# RPi.net
KiCad netlist of a schematic drawn in EAGLE
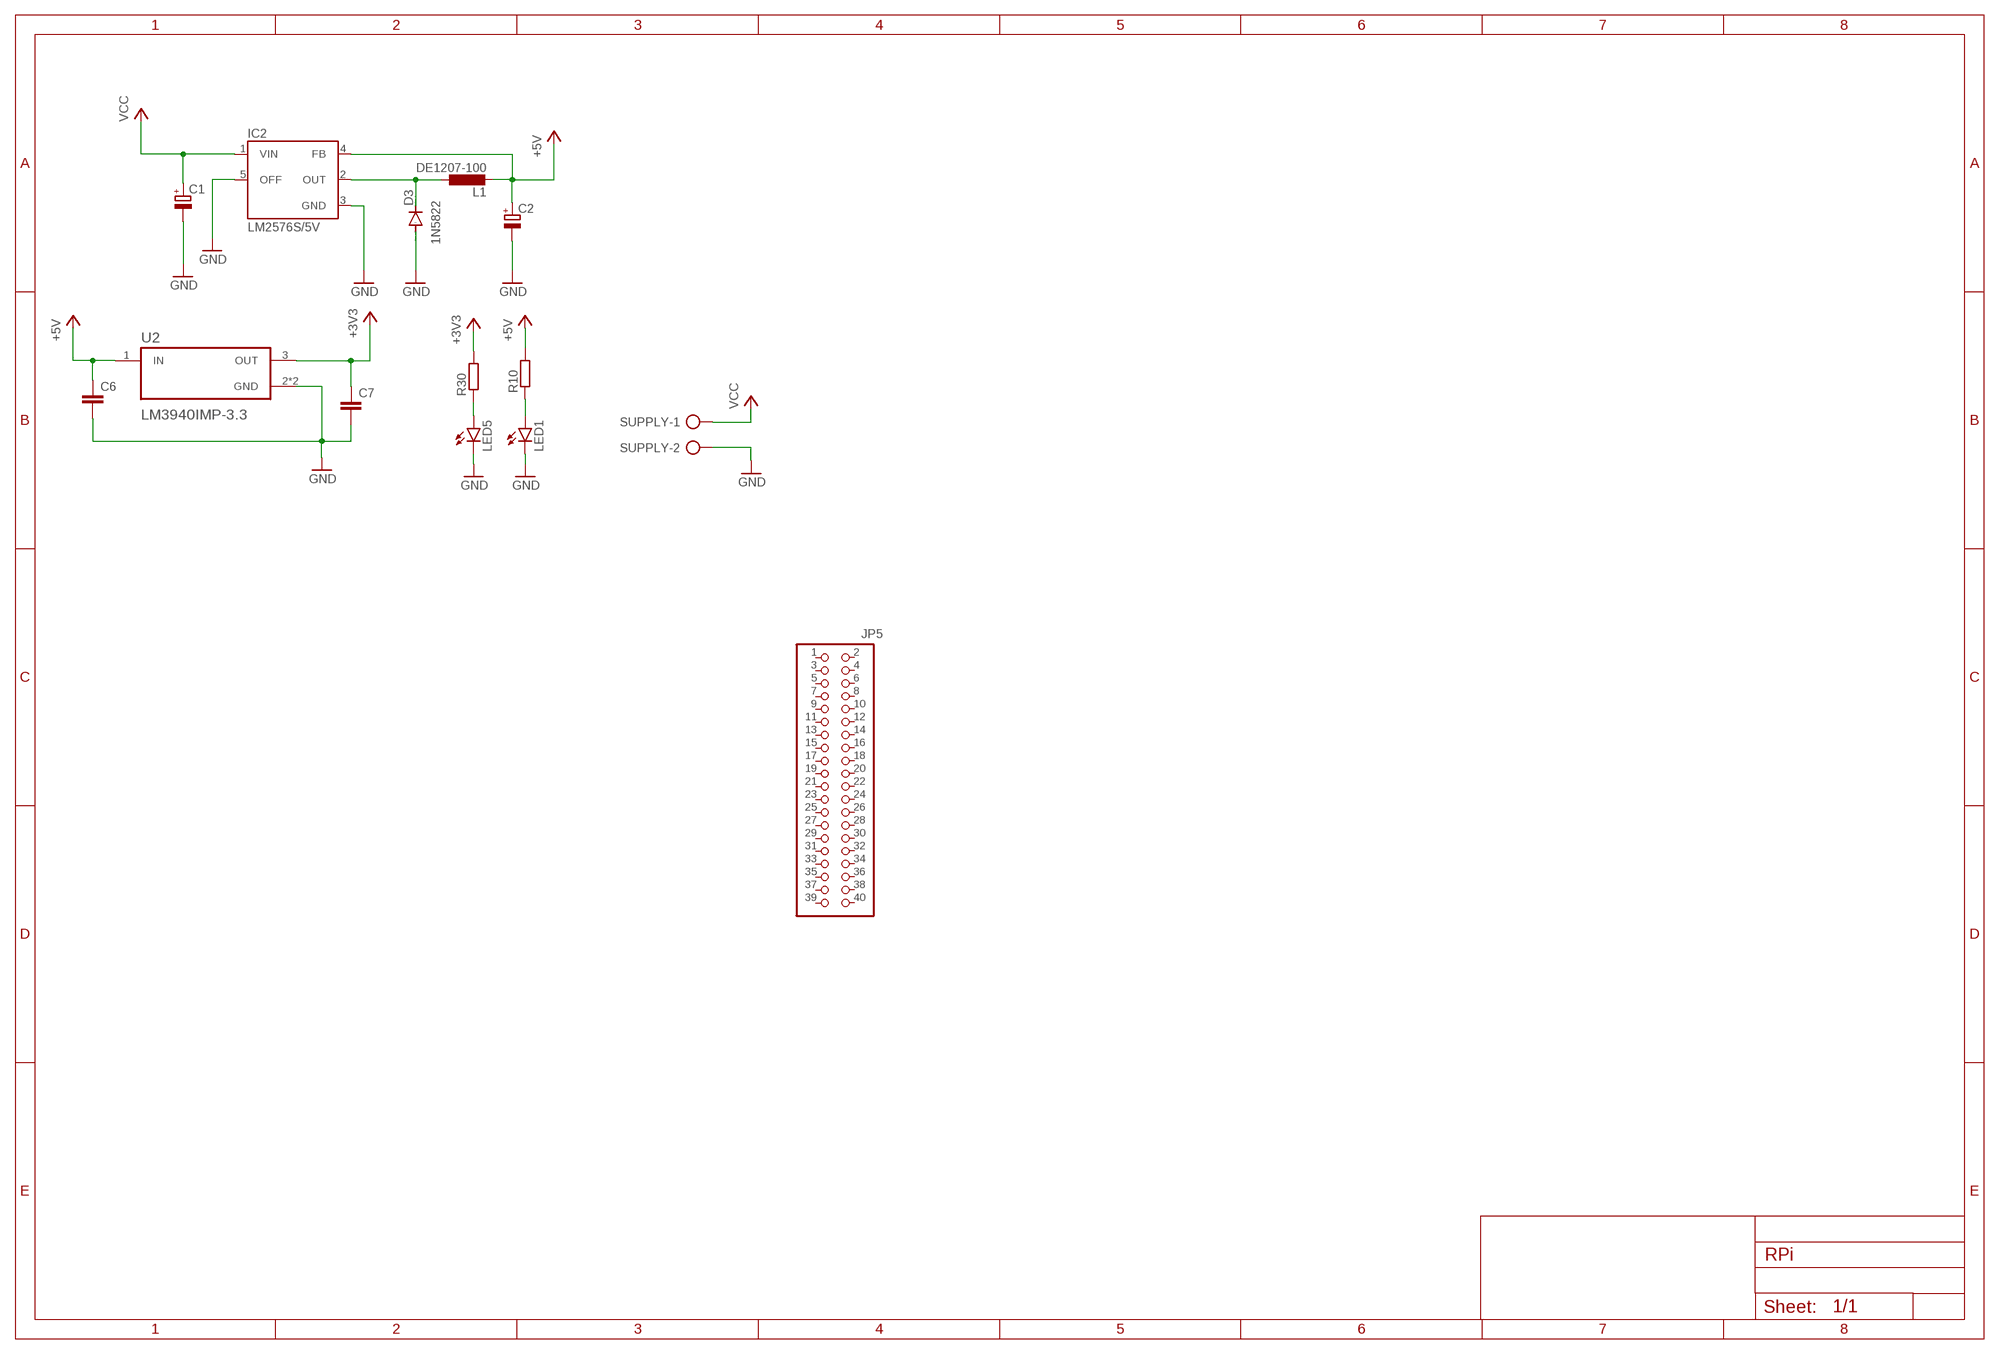
[diagram p0: schematic, sheet 1]

(export (version "E")
  (design (tool "Eeschema 10.0.6"))
  (components
    (comp (ref "C1")
      (value "CPOL-EUE2.5-6")
      (footprint "eagle-import:E2,5-6")
      (libsource (lib "eagle-import") (part "CPOL-EUE2.5-6"))
    )
    (comp (ref "C2")
      (value "CPOL-EUE2.5-6")
      (footprint "eagle-import:E2,5-6")
      (libsource (lib "eagle-import") (part "CPOL-EUE2.5-6"))
    )
    (comp (ref "C6")
      (value "C-EUC0805K")
      (footprint "eagle-import:C0805K")
      (libsource (lib "eagle-import") (part "C-EUC0805K"))
    )
    (comp (ref "C7")
      (value "C-EUC0805K")
      (footprint "eagle-import:C0805K")
      (libsource (lib "eagle-import") (part "C-EUC0805K"))
    )
    (comp (ref "D3")
      (value "1N5822")
      (footprint "eagle-import:DO41-10")
      (libsource (lib "eagle-import") (part "1N4004"))
    )
    (comp (ref "IC2")
      (value "LM2576S/5V")
      (footprint "eagle-import:TO263-5")
      (libsource (lib "eagle-import") (part "LM2576S"))
    )
    (comp (ref "JP5")
      (value "PINHD-2X20")
      (footprint "eagle-import:2X20")
      (libsource (lib "eagle-import") (part "PINHD-2X20"))
    )
    (comp (ref "L1")
      (value "DE1207-100")
      (footprint "eagle-import:DE1207")
      (libsource (lib "eagle-import") (part "DE1207-100"))
    )
    (comp (ref "LED1")
      (value "LEDSML0805")
      (footprint "eagle-import:SML0805")
      (libsource (lib "eagle-import") (part "LEDSML0805"))
    )
    (comp (ref "LED5")
      (value "LEDSML0805")
      (footprint "eagle-import:SML0805")
      (libsource (lib "eagle-import") (part "LEDSML0805"))
    )
    (comp (ref "R10")
      (value "R-EU_R0805")
      (footprint "eagle-import:R0805")
      (libsource (lib "eagle-import") (part "R-EU_R0805"))
    )
    (comp (ref "R30")
      (value "R-EU_R0805")
      (footprint "eagle-import:R0805")
      (libsource (lib "eagle-import") (part "R-EU_R0805"))
    )
    (comp (ref "SUPPLY")
      (value "AK500/2-H")
      (footprint "eagle-import:AK500_2-H")
      (libsource (lib "eagle-import") (part "AK500/2-H"))
    )
    (comp (ref "U2")
      (value "LM3940IMP-3.3")
      (footprint "eagle-import:SOT230P700X180-4N")
      (fields (field (name "MF") "Texas Instruments"))
      (libsource (lib "eagle-import") (part "LM3940IMP-3.3"))
    )
  )
  (nets
    (net (code "1") (name "+3V3") (class "Default")
      (node (ref "C7") (pin "1") (pinfunction "1_1") (pintype "passive"))
      (node (ref "R30") (pin "2") (pinfunction "2_2") (pintype "passive"))
      (node (ref "U2") (pin "3") (pinfunction "OUT_3") (pintype "output"))
    )
    (net (code "2") (name "+5V") (class "Default")
      (node (ref "C2") (pin "+") (pinfunction "+_+") (pintype "passive"))
      (node (ref "C6") (pin "1") (pinfunction "1_1") (pintype "passive"))
      (node (ref "IC2") (pin "4") (pinfunction "FB_4") (pintype "input"))
      (node (ref "L1") (pin "2") (pinfunction "2_2") (pintype "passive"))
      (node (ref "R10") (pin "2") (pinfunction "2_2") (pintype "passive"))
      (node (ref "U2") (pin "1") (pinfunction "IN_1") (pintype "input"))
    )
    (net (code "3") (name "GND") (class "Default")
      (node (ref "C1") (pin "-") (pinfunction "-_-") (pintype "passive"))
      (node (ref "C2") (pin "-") (pinfunction "-_-") (pintype "passive"))
      (node (ref "C6") (pin "2") (pinfunction "2_2") (pintype "passive"))
      (node (ref "C7") (pin "2") (pinfunction "2_2") (pintype "passive"))
      (node (ref "D3") (pin "A") (pinfunction "A_A") (pintype "passive"))
      (node (ref "IC2") (pin "3") (pinfunction "GND_3") (pintype "power_in"))
      (node (ref "IC2") (pin "5") (pinfunction "OFF_5") (pintype "input"))
      (node (ref "LED1") (pin "C") (pinfunction "C_C") (pintype "passive"))
      (node (ref "LED5") (pin "C") (pinfunction "C_C") (pintype "passive"))
      (node (ref "SUPPLY") (pin "2") (pinfunction "KL_2") (pintype "passive"))
      (node (ref "U2") (pin "2") (pinfunction "GND_2") (pintype "power_in"))
      (node (ref "U2") (pin "4") (pinfunction "GND_4") (pintype "power_in"))
    )
    (net (code "4") (name "Net-(IC2-OUT)") (class "Default")
      (node (ref "D3") (pin "C") (pinfunction "C_C") (pintype "passive"))
      (node (ref "IC2") (pin "2") (pinfunction "OUT_2") (pintype "output"))
      (node (ref "L1") (pin "1") (pinfunction "1_1") (pintype "passive"))
    )
    (net (code "5") (name "Net-(LED1-PadA)") (class "Default")
      (node (ref "LED1") (pin "A") (pinfunction "A_A") (pintype "passive"))
      (node (ref "R10") (pin "1") (pinfunction "1_1") (pintype "passive"))
    )
    (net (code "6") (name "Net-(LED5-PadA)") (class "Default")
      (node (ref "LED5") (pin "A") (pinfunction "A_A") (pintype "passive"))
      (node (ref "R30") (pin "1") (pinfunction "1_1") (pintype "passive"))
    )
    (net (code "7") (name "VCC") (class "Default")
      (node (ref "C1") (pin "+") (pinfunction "+_+") (pintype "passive"))
      (node (ref "IC2") (pin "1") (pinfunction "VIN_1") (pintype "power_in"))
      (node (ref "SUPPLY") (pin "1") (pinfunction "KL_1") (pintype "passive"))
    )
    (net (code "8") (name "unconnected-(JP5-Pad1)") (class "Default")
      (node (ref "JP5") (pin "1") (pinfunction "1_1") (pintype "passive"))
    )
    (net (code "9") (name "unconnected-(JP5-Pad2)") (class "Default")
      (node (ref "JP5") (pin "2") (pinfunction "2_2") (pintype "passive"))
    )
    (net (code "10") (name "unconnected-(JP5-Pad3)") (class "Default")
      (node (ref "JP5") (pin "3") (pinfunction "3_3") (pintype "passive"))
    )
    (net (code "11") (name "unconnected-(JP5-Pad4)") (class "Default")
      (node (ref "JP5") (pin "4") (pinfunction "4_4") (pintype "passive"))
    )
    (net (code "12") (name "unconnected-(JP5-Pad5)") (class "Default")
      (node (ref "JP5") (pin "5") (pinfunction "5_5") (pintype "passive"))
    )
    (net (code "13") (name "unconnected-(JP5-Pad6)") (class "Default")
      (node (ref "JP5") (pin "6") (pinfunction "6_6") (pintype "passive"))
    )
    (net (code "14") (name "unconnected-(JP5-Pad7)") (class "Default")
      (node (ref "JP5") (pin "7") (pinfunction "7_7") (pintype "passive"))
    )
    (net (code "15") (name "unconnected-(JP5-Pad8)") (class "Default")
      (node (ref "JP5") (pin "8") (pinfunction "8_8") (pintype "passive"))
    )
    (net (code "16") (name "unconnected-(JP5-Pad9)") (class "Default")
      (node (ref "JP5") (pin "9") (pinfunction "9_9") (pintype "passive"))
    )
    (net (code "17") (name "unconnected-(JP5-Pad10)") (class "Default")
      (node (ref "JP5") (pin "10") (pinfunction "10_10") (pintype "passive"))
    )
    (net (code "18") (name "unconnected-(JP5-Pad11)") (class "Default")
      (node (ref "JP5") (pin "11") (pinfunction "11_11") (pintype "passive"))
    )
    (net (code "19") (name "unconnected-(JP5-Pad12)") (class "Default")
      (node (ref "JP5") (pin "12") (pinfunction "12_12") (pintype "passive"))
    )
    (net (code "20") (name "unconnected-(JP5-Pad13)") (class "Default")
      (node (ref "JP5") (pin "13") (pinfunction "13_13") (pintype "passive"))
    )
    (net (code "21") (name "unconnected-(JP5-Pad14)") (class "Default")
      (node (ref "JP5") (pin "14") (pinfunction "14_14") (pintype "passive"))
    )
    (net (code "22") (name "unconnected-(JP5-Pad15)") (class "Default")
      (node (ref "JP5") (pin "15") (pinfunction "15_15") (pintype "passive"))
    )
    (net (code "23") (name "unconnected-(JP5-Pad16)") (class "Default")
      (node (ref "JP5") (pin "16") (pinfunction "16_16") (pintype "passive"))
    )
    (net (code "24") (name "unconnected-(JP5-Pad17)") (class "Default")
      (node (ref "JP5") (pin "17") (pinfunction "17_17") (pintype "passive"))
    )
    (net (code "25") (name "unconnected-(JP5-Pad18)") (class "Default")
      (node (ref "JP5") (pin "18") (pinfunction "18_18") (pintype "passive"))
    )
    (net (code "26") (name "unconnected-(JP5-Pad19)") (class "Default")
      (node (ref "JP5") (pin "19") (pinfunction "19_19") (pintype "passive"))
    )
    (net (code "27") (name "unconnected-(JP5-Pad20)") (class "Default")
      (node (ref "JP5") (pin "20") (pinfunction "20_20") (pintype "passive"))
    )
    (net (code "28") (name "unconnected-(JP5-Pad21)") (class "Default")
      (node (ref "JP5") (pin "21") (pinfunction "21_21") (pintype "passive"))
    )
    (net (code "29") (name "unconnected-(JP5-Pad22)") (class "Default")
      (node (ref "JP5") (pin "22") (pinfunction "22_22") (pintype "passive"))
    )
    (net (code "30") (name "unconnected-(JP5-Pad23)") (class "Default")
      (node (ref "JP5") (pin "23") (pinfunction "23_23") (pintype "passive"))
    )
    (net (code "31") (name "unconnected-(JP5-Pad24)") (class "Default")
      (node (ref "JP5") (pin "24") (pinfunction "24_24") (pintype "passive"))
    )
    (net (code "32") (name "unconnected-(JP5-Pad25)") (class "Default")
      (node (ref "JP5") (pin "25") (pinfunction "25_25") (pintype "passive"))
    )
    (net (code "33") (name "unconnected-(JP5-Pad26)") (class "Default")
      (node (ref "JP5") (pin "26") (pinfunction "26_26") (pintype "passive"))
    )
    (net (code "34") (name "unconnected-(JP5-Pad27)") (class "Default")
      (node (ref "JP5") (pin "27") (pinfunction "27_27") (pintype "passive"))
    )
    (net (code "35") (name "unconnected-(JP5-Pad28)") (class "Default")
      (node (ref "JP5") (pin "28") (pinfunction "28_28") (pintype "passive"))
    )
    (net (code "36") (name "unconnected-(JP5-Pad29)") (class "Default")
      (node (ref "JP5") (pin "29") (pinfunction "29_29") (pintype "passive"))
    )
    (net (code "37") (name "unconnected-(JP5-Pad30)") (class "Default")
      (node (ref "JP5") (pin "30") (pinfunction "30_30") (pintype "passive"))
    )
    (net (code "38") (name "unconnected-(JP5-Pad31)") (class "Default")
      (node (ref "JP5") (pin "31") (pinfunction "31_31") (pintype "passive"))
    )
    (net (code "39") (name "unconnected-(JP5-Pad32)") (class "Default")
      (node (ref "JP5") (pin "32") (pinfunction "32_32") (pintype "passive"))
    )
    (net (code "40") (name "unconnected-(JP5-Pad33)") (class "Default")
      (node (ref "JP5") (pin "33") (pinfunction "33_33") (pintype "passive"))
    )
    (net (code "41") (name "unconnected-(JP5-Pad34)") (class "Default")
      (node (ref "JP5") (pin "34") (pinfunction "34_34") (pintype "passive"))
    )
    (net (code "42") (name "unconnected-(JP5-Pad35)") (class "Default")
      (node (ref "JP5") (pin "35") (pinfunction "35_35") (pintype "passive"))
    )
    (net (code "43") (name "unconnected-(JP5-Pad36)") (class "Default")
      (node (ref "JP5") (pin "36") (pinfunction "36_36") (pintype "passive"))
    )
    (net (code "44") (name "unconnected-(JP5-Pad37)") (class "Default")
      (node (ref "JP5") (pin "37") (pinfunction "37_37") (pintype "passive"))
    )
    (net (code "45") (name "unconnected-(JP5-Pad38)") (class "Default")
      (node (ref "JP5") (pin "38") (pinfunction "38_38") (pintype "passive"))
    )
    (net (code "46") (name "unconnected-(JP5-Pad39)") (class "Default")
      (node (ref "JP5") (pin "39") (pinfunction "39_39") (pintype "passive"))
    )
    (net (code "47") (name "unconnected-(JP5-Pad40)") (class "Default")
      (node (ref "JP5") (pin "40") (pinfunction "40_40") (pintype "passive"))
    )
  )
)
